# Top_level.net
KiCad netlist of a schematic drawn in Altium Designer
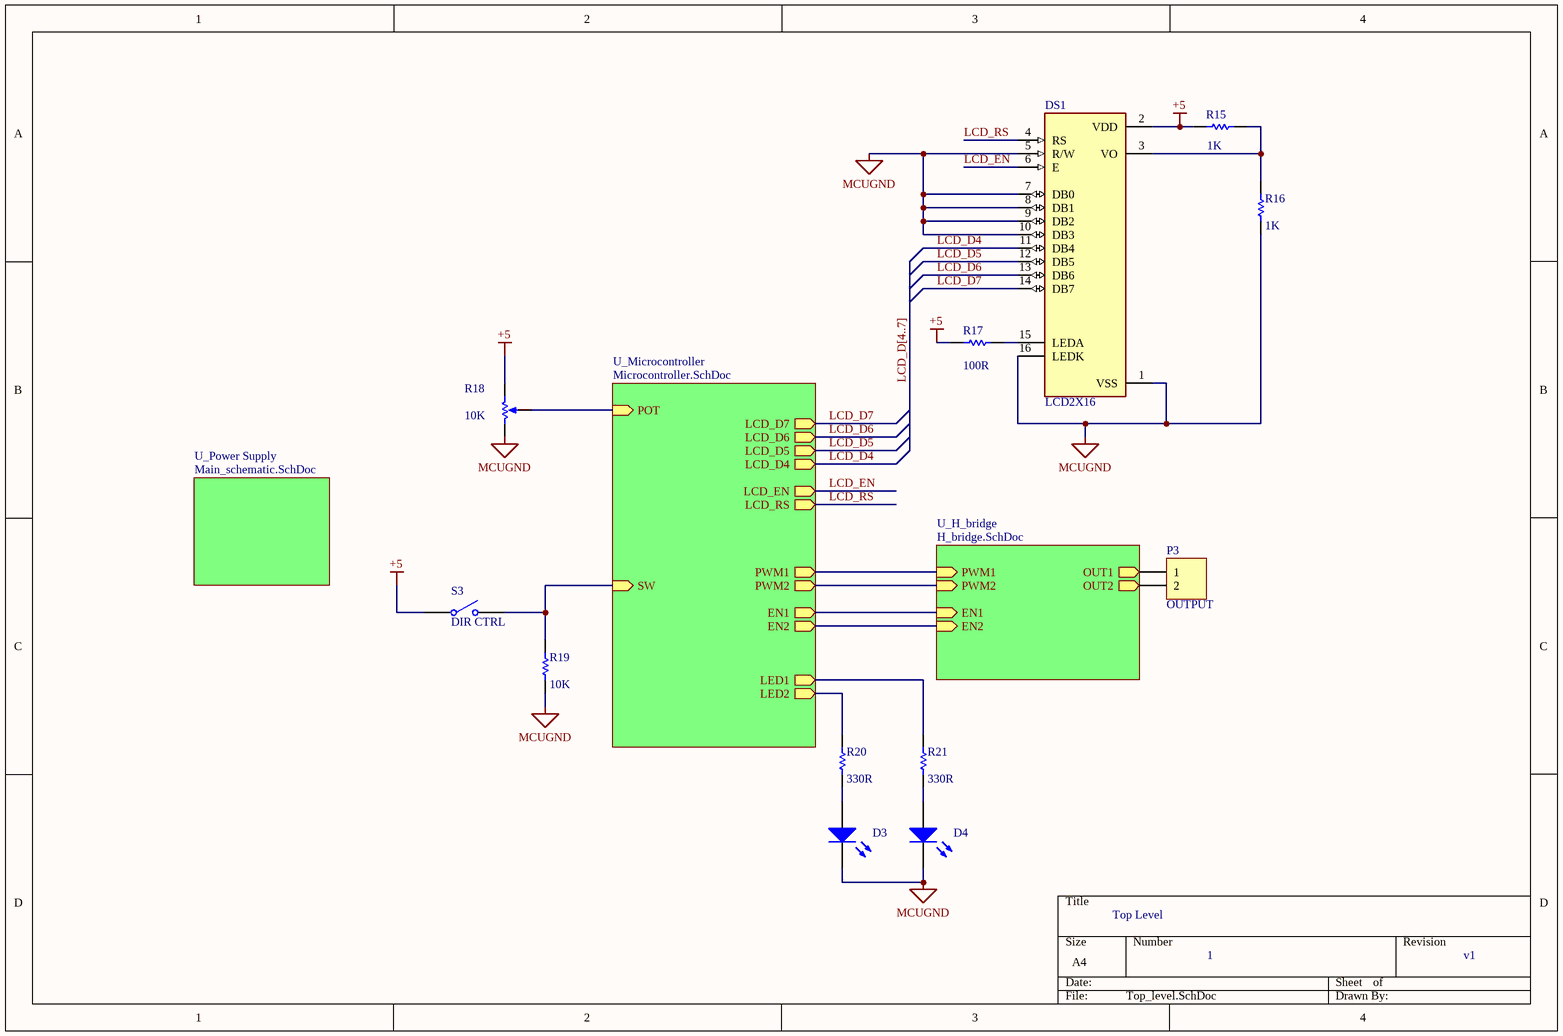
[diagram p0: Top_level.SchDoc]

(export (version "E")
  (design (tool "Eeschema 10.0.6"))
  (components
    (comp (ref "D3")
      (value "LED1")
      (footprint "LED-1")
      (description "Typical RED GaAs LED")
      (fields (field (name "PUBLISHER") "Altium Limited"))
      (libsource (lib "Miscellaneous Devices") (part "LED1"))
    )
    (comp (ref "D4")
      (value "LED1")
      (footprint "LED-1")
      (description "Typical RED GaAs LED")
      (fields (field (name "PUBLISHER") "Altium Limited"))
      (libsource (lib "Miscellaneous Devices") (part "LED1"))
    )
    (comp (ref "DS1")
      (value "LCD2X16")
      (footprint "LCD_LCD2X16")
      (description "Display; Display: LCD 2x16 characters (blue backlight)")
      (fields (field (name "MF") "mikroElektronika"))
      (libsource (lib "LCD2X16") (part "LCD2X16"))
    )
    (comp (ref "P3")
      (value "OUTPUT")
      (footprint "HDR1X2")
      (description "Header, 2-Pin")
      (fields (field (name "PUBLISHER") "Altium Limited"))
      (libsource (lib "Miscellaneous Connectors") (part "Header 2"))
    )
    (comp (ref "R15")
      (value "1K")
      (footprint "AXIAL-0.3")
      (description "Resistor")
      (fields (field (name "Comment") "Res1") (field (name "PUBLISHER") "Altium Limited"))
      (libsource (lib "Miscellaneous Devices") (part "Res1"))
    )
    (comp (ref "R16")
      (value "1K")
      (footprint "AXIAL-0.3")
      (description "Resistor")
      (fields (field (name "Comment") "Res1") (field (name "PUBLISHER") "Altium Limited"))
      (libsource (lib "Miscellaneous Devices") (part "Res1"))
    )
    (comp (ref "R17")
      (value "100R")
      (footprint "AXIAL-0.3")
      (description "Resistor")
      (fields (field (name "Comment") "Res1") (field (name "PUBLISHER") "Altium Limited"))
      (libsource (lib "Miscellaneous Devices") (part "Res1"))
    )
    (comp (ref "R18")
      (value "10K")
      (footprint "VR5")
      (description "Potentiometer")
      (fields (field (name "Comment") "RPot") (field (name "PUBLISHER") "Altium Limited"))
      (libsource (lib "Miscellaneous Devices") (part "RPot"))
    )
    (comp (ref "R19")
      (value "10K")
      (footprint "AXIAL-0.3")
      (description "Resistor")
      (fields (field (name "Comment") "Res1") (field (name "PUBLISHER") "Altium Limited"))
      (libsource (lib "Miscellaneous Devices") (part "Res1"))
    )
    (comp (ref "R20")
      (value "330R")
      (footprint "AXIAL-0.3")
      (description "Resistor")
      (fields (field (name "Comment") "Res1") (field (name "PUBLISHER") "Altium Limited"))
      (libsource (lib "Miscellaneous Devices") (part "Res1"))
    )
    (comp (ref "R21")
      (value "330R")
      (footprint "AXIAL-0.3")
      (description "Resistor")
      (fields (field (name "Comment") "Res1") (field (name "PUBLISHER") "Altium Limited"))
      (libsource (lib "Miscellaneous Devices") (part "Res1"))
    )
    (comp (ref "S3")
      (value "DIR CTRL")
      (footprint "SPST-2")
      (description "Single-Pole, Single-Throw Switch")
      (fields (field (name "PUBLISHER") "Altium Limited"))
      (libsource (lib "Miscellaneous Devices") (part "SW-SPST"))
    )
  )
  (nets
    (net (code "1") (name "+5") (class "Default")
      (node (ref "DS1") (pin "2") (pinfunction "VDD_2") (pintype "power_in"))
      (node (ref "R15") (pin "1") (pinfunction "1_1") (pintype "passive"))
      (node (ref "R17") (pin "1") (pinfunction "1_1") (pintype "passive"))
      (node (ref "R18") (pin "1") (pinfunction "TOP_1") (pintype "passive"))
      (node (ref "S3") (pin "1") (pinfunction "COMMON_1") (pintype "passive"))
    )
    (net (code "4") (name "/LCD_D4") (class "Default")
      (node (ref "DS1") (pin "11") (pinfunction "DB4_11") (pintype "bidirectional"))
    )
    (net (code "5") (name "/LCD_D5") (class "Default")
      (node (ref "DS1") (pin "12") (pinfunction "DB5_12") (pintype "bidirectional"))
    )
    (net (code "6") (name "/LCD_D6") (class "Default")
      (node (ref "DS1") (pin "13") (pinfunction "DB6_13") (pintype "bidirectional"))
    )
    (net (code "7") (name "/LCD_D7") (class "Default")
      (node (ref "DS1") (pin "14") (pinfunction "DB7_14") (pintype "bidirectional"))
    )
    (net (code "9") (name "/LCD_EN") (class "Default")
      (node (ref "DS1") (pin "6") (pinfunction "E_6") (pintype "input"))
    )
    (net (code "10") (name "/LCD_RS") (class "Default")
      (node (ref "DS1") (pin "4") (pinfunction "RS_4") (pintype "input"))
    )
    (net (code "11") (name "/LED1") (class "Default")
      (node (ref "R21") (pin "2") (pinfunction "2_2") (pintype "passive"))
    )
    (net (code "12") (name "/LED2") (class "Default")
      (node (ref "R20") (pin "2") (pinfunction "2_2") (pintype "passive"))
    )
    (net (code "13") (name "/OUT1") (class "Default")
      (node (ref "P3") (pin "1") (pinfunction "1_1") (pintype "passive"))
    )
    (net (code "14") (name "/OUT2") (class "Default")
      (node (ref "P3") (pin "2") (pinfunction "2_2") (pintype "passive"))
    )
    (net (code "15") (name "/POT") (class "Default")
      (node (ref "R18") (pin "3") (pinfunction "TAP_3") (pintype "passive"))
    )
    (net (code "18") (name "/SW") (class "Default")
      (node (ref "R19") (pin "2") (pinfunction "2_2") (pintype "passive"))
      (node (ref "S3") (pin "2") (pinfunction "NO_2") (pintype "passive"))
    )
    (net (code "19") (name "MCUGND") (class "Default")
      (node (ref "D3") (pin "2") (pinfunction "K_2") (pintype "passive"))
      (node (ref "D4") (pin "2") (pinfunction "K_2") (pintype "passive"))
      (node (ref "DS1") (pin "1") (pinfunction "VSS_1") (pintype "power_in"))
      (node (ref "DS1") (pin "10") (pinfunction "DB3_10") (pintype "bidirectional"))
      (node (ref "DS1") (pin "16") (pinfunction "LEDK_16") (pintype "passive"))
      (node (ref "DS1") (pin "5") (pinfunction "R/W_5") (pintype "input"))
      (node (ref "DS1") (pin "7") (pinfunction "DB0_7") (pintype "bidirectional"))
      (node (ref "DS1") (pin "8") (pinfunction "DB1_8") (pintype "bidirectional"))
      (node (ref "DS1") (pin "9") (pinfunction "DB2_9") (pintype "bidirectional"))
      (node (ref "R16") (pin "1") (pinfunction "1_1") (pintype "passive"))
      (node (ref "R18") (pin "2") (pinfunction "BOT_2") (pintype "passive"))
      (node (ref "R19") (pin "1") (pinfunction "1_1") (pintype "passive"))
    )
    (net (code "20") (name "Net-(D3-A)") (class "Default")
      (node (ref "D3") (pin "1") (pinfunction "A_1") (pintype "passive"))
      (node (ref "R20") (pin "1") (pinfunction "1_1") (pintype "passive"))
    )
    (net (code "21") (name "Net-(D4-A)") (class "Default")
      (node (ref "D4") (pin "1") (pinfunction "A_1") (pintype "passive"))
      (node (ref "R21") (pin "1") (pinfunction "1_1") (pintype "passive"))
    )
    (net (code "22") (name "Net-(DS1-LEDA)") (class "Default")
      (node (ref "DS1") (pin "15") (pinfunction "LEDA_15") (pintype "passive"))
      (node (ref "R17") (pin "2") (pinfunction "2_2") (pintype "passive"))
    )
    (net (code "23") (name "Net-(DS1-VO)") (class "Default")
      (node (ref "DS1") (pin "3") (pinfunction "VO_3") (pintype "passive"))
      (node (ref "R15") (pin "2") (pinfunction "2_2") (pintype "passive"))
      (node (ref "R16") (pin "2") (pinfunction "2_2") (pintype "passive"))
    )
  )
)
